# 20200123_second_Platine_Power.net
KiCad netlist of a schematic drawn in EAGLE
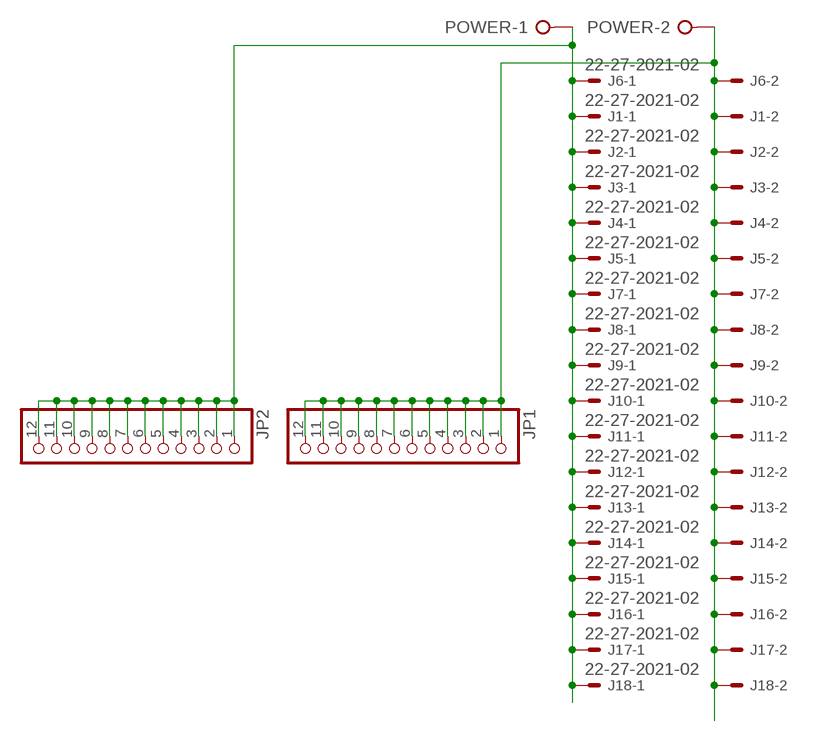
[diagram p0: schematic, sheet 1]

(export (version "E")
  (design (tool "Eeschema 10.0.6"))
  (components
    (comp (ref "J1")
      (value "22-27-2021-02")
      (footprint "eagle-import:6410-02")
      (libsource (lib "eagle-import") (part "22-?-0227-2021"))
    )
    (comp (ref "J2")
      (value "22-27-2021-02")
      (footprint "eagle-import:6410-02")
      (libsource (lib "eagle-import") (part "22-?-0227-2021"))
    )
    (comp (ref "J3")
      (value "22-27-2021-02")
      (footprint "eagle-import:6410-02")
      (libsource (lib "eagle-import") (part "22-?-0227-2021"))
    )
    (comp (ref "J4")
      (value "22-27-2021-02")
      (footprint "eagle-import:6410-02")
      (libsource (lib "eagle-import") (part "22-?-0227-2021"))
    )
    (comp (ref "J5")
      (value "22-27-2021-02")
      (footprint "eagle-import:6410-02")
      (libsource (lib "eagle-import") (part "22-?-0227-2021"))
    )
    (comp (ref "J6")
      (value "22-27-2021-02")
      (footprint "eagle-import:6410-02")
      (libsource (lib "eagle-import") (part "22-?-0227-2021"))
    )
    (comp (ref "J7")
      (value "22-27-2021-02")
      (footprint "eagle-import:6410-02")
      (libsource (lib "eagle-import") (part "22-?-0227-2021"))
    )
    (comp (ref "J8")
      (value "22-27-2021-02")
      (footprint "eagle-import:6410-02")
      (libsource (lib "eagle-import") (part "22-?-0227-2021"))
    )
    (comp (ref "J9")
      (value "22-27-2021-02")
      (footprint "eagle-import:6410-02")
      (libsource (lib "eagle-import") (part "22-?-0227-2021"))
    )
    (comp (ref "J10")
      (value "22-27-2021-02")
      (footprint "eagle-import:6410-02")
      (libsource (lib "eagle-import") (part "22-?-0227-2021"))
    )
    (comp (ref "J11")
      (value "22-27-2021-02")
      (footprint "eagle-import:6410-02")
      (libsource (lib "eagle-import") (part "22-?-0227-2021"))
    )
    (comp (ref "J12")
      (value "22-27-2021-02")
      (footprint "eagle-import:6410-02")
      (libsource (lib "eagle-import") (part "22-?-0227-2021"))
    )
    (comp (ref "J13")
      (value "22-27-2021-02")
      (footprint "eagle-import:6410-02")
      (libsource (lib "eagle-import") (part "22-?-0227-2021"))
    )
    (comp (ref "J14")
      (value "22-27-2021-02")
      (footprint "eagle-import:6410-02")
      (libsource (lib "eagle-import") (part "22-?-0227-2021"))
    )
    (comp (ref "J15")
      (value "22-27-2021-02")
      (footprint "eagle-import:6410-02")
      (libsource (lib "eagle-import") (part "22-?-0227-2021"))
    )
    (comp (ref "J16")
      (value "22-27-2021-02")
      (footprint "eagle-import:6410-02")
      (libsource (lib "eagle-import") (part "22-?-0227-2021"))
    )
    (comp (ref "J17")
      (value "22-27-2021-02")
      (footprint "eagle-import:6410-02")
      (libsource (lib "eagle-import") (part "22-?-0227-2021"))
    )
    (comp (ref "J18")
      (value "22-27-2021-02")
      (footprint "eagle-import:6410-02")
      (libsource (lib "eagle-import") (part "22-?-0227-2021"))
    )
    (comp (ref "JP1")
      (value "PINHD-1X12")
      (footprint "eagle-import:1X12")
      (libsource (lib "eagle-import") (part "PINHD-1X12"))
    )
    (comp (ref "JP2")
      (value "PINHD-1X12")
      (footprint "eagle-import:1X12")
      (libsource (lib "eagle-import") (part "PINHD-1X12"))
    )
    (comp (ref "POWER")
      (value "W237-02P")
      (footprint "eagle-import:W237-132")
      (libsource (lib "eagle-import") (part "W237-02P"))
    )
  )
  (nets
    (net (code "1") (name "Net-(J10A-S)") (class "Default")
      (node (ref "J1") (pin "1") (pinfunction "S_1") (pintype "passive"))
      (node (ref "J10") (pin "1") (pinfunction "S_1") (pintype "passive"))
      (node (ref "J11") (pin "1") (pinfunction "S_1") (pintype "passive"))
      (node (ref "J12") (pin "1") (pinfunction "S_1") (pintype "passive"))
      (node (ref "J13") (pin "1") (pinfunction "S_1") (pintype "passive"))
      (node (ref "J14") (pin "1") (pinfunction "S_1") (pintype "passive"))
      (node (ref "J15") (pin "1") (pinfunction "S_1") (pintype "passive"))
      (node (ref "J16") (pin "1") (pinfunction "S_1") (pintype "passive"))
      (node (ref "J17") (pin "1") (pinfunction "S_1") (pintype "passive"))
      (node (ref "J18") (pin "1") (pinfunction "S_1") (pintype "passive"))
      (node (ref "J2") (pin "1") (pinfunction "S_1") (pintype "passive"))
      (node (ref "J3") (pin "1") (pinfunction "S_1") (pintype "passive"))
      (node (ref "J4") (pin "1") (pinfunction "S_1") (pintype "passive"))
      (node (ref "J5") (pin "1") (pinfunction "S_1") (pintype "passive"))
      (node (ref "J6") (pin "1") (pinfunction "S_1") (pintype "passive"))
      (node (ref "J7") (pin "1") (pinfunction "S_1") (pintype "passive"))
      (node (ref "J8") (pin "1") (pinfunction "S_1") (pintype "passive"))
      (node (ref "J9") (pin "1") (pinfunction "S_1") (pintype "passive"))
      (node (ref "JP2") (pin "1") (pinfunction "1_1") (pintype "passive"))
      (node (ref "JP2") (pin "10") (pinfunction "10_10") (pintype "passive"))
      (node (ref "JP2") (pin "11") (pinfunction "11_11") (pintype "passive"))
      (node (ref "JP2") (pin "12") (pinfunction "12_12") (pintype "passive"))
      (node (ref "JP2") (pin "2") (pinfunction "2_2") (pintype "passive"))
      (node (ref "JP2") (pin "3") (pinfunction "3_3") (pintype "passive"))
      (node (ref "JP2") (pin "4") (pinfunction "4_4") (pintype "passive"))
      (node (ref "JP2") (pin "5") (pinfunction "5_5") (pintype "passive"))
      (node (ref "JP2") (pin "6") (pinfunction "6_6") (pintype "passive"))
      (node (ref "JP2") (pin "7") (pinfunction "7_7") (pintype "passive"))
      (node (ref "JP2") (pin "8") (pinfunction "8_8") (pintype "passive"))
      (node (ref "JP2") (pin "9") (pinfunction "9_9") (pintype "passive"))
      (node (ref "POWER") (pin "1") (pinfunction "KL_1") (pintype "passive"))
    )
    (net (code "2") (name "Net-(J10B-S)") (class "Default")
      (node (ref "J1") (pin "2") (pinfunction "S_2") (pintype "passive"))
      (node (ref "J10") (pin "2") (pinfunction "S_2") (pintype "passive"))
      (node (ref "J11") (pin "2") (pinfunction "S_2") (pintype "passive"))
      (node (ref "J12") (pin "2") (pinfunction "S_2") (pintype "passive"))
      (node (ref "J13") (pin "2") (pinfunction "S_2") (pintype "passive"))
      (node (ref "J14") (pin "2") (pinfunction "S_2") (pintype "passive"))
      (node (ref "J15") (pin "2") (pinfunction "S_2") (pintype "passive"))
      (node (ref "J16") (pin "2") (pinfunction "S_2") (pintype "passive"))
      (node (ref "J17") (pin "2") (pinfunction "S_2") (pintype "passive"))
      (node (ref "J18") (pin "2") (pinfunction "S_2") (pintype "passive"))
      (node (ref "J2") (pin "2") (pinfunction "S_2") (pintype "passive"))
      (node (ref "J3") (pin "2") (pinfunction "S_2") (pintype "passive"))
      (node (ref "J4") (pin "2") (pinfunction "S_2") (pintype "passive"))
      (node (ref "J5") (pin "2") (pinfunction "S_2") (pintype "passive"))
      (node (ref "J6") (pin "2") (pinfunction "S_2") (pintype "passive"))
      (node (ref "J7") (pin "2") (pinfunction "S_2") (pintype "passive"))
      (node (ref "J8") (pin "2") (pinfunction "S_2") (pintype "passive"))
      (node (ref "J9") (pin "2") (pinfunction "S_2") (pintype "passive"))
      (node (ref "JP1") (pin "1") (pinfunction "1_1") (pintype "passive"))
      (node (ref "JP1") (pin "10") (pinfunction "10_10") (pintype "passive"))
      (node (ref "JP1") (pin "11") (pinfunction "11_11") (pintype "passive"))
      (node (ref "JP1") (pin "12") (pinfunction "12_12") (pintype "passive"))
      (node (ref "JP1") (pin "2") (pinfunction "2_2") (pintype "passive"))
      (node (ref "JP1") (pin "3") (pinfunction "3_3") (pintype "passive"))
      (node (ref "JP1") (pin "4") (pinfunction "4_4") (pintype "passive"))
      (node (ref "JP1") (pin "5") (pinfunction "5_5") (pintype "passive"))
      (node (ref "JP1") (pin "6") (pinfunction "6_6") (pintype "passive"))
      (node (ref "JP1") (pin "7") (pinfunction "7_7") (pintype "passive"))
      (node (ref "JP1") (pin "8") (pinfunction "8_8") (pintype "passive"))
      (node (ref "JP1") (pin "9") (pinfunction "9_9") (pintype "passive"))
      (node (ref "POWER") (pin "2") (pinfunction "KL_2") (pintype "passive"))
    )
  )
)
